# STM32F405.net
KiCad netlist of a schematic drawn in Altium Designer
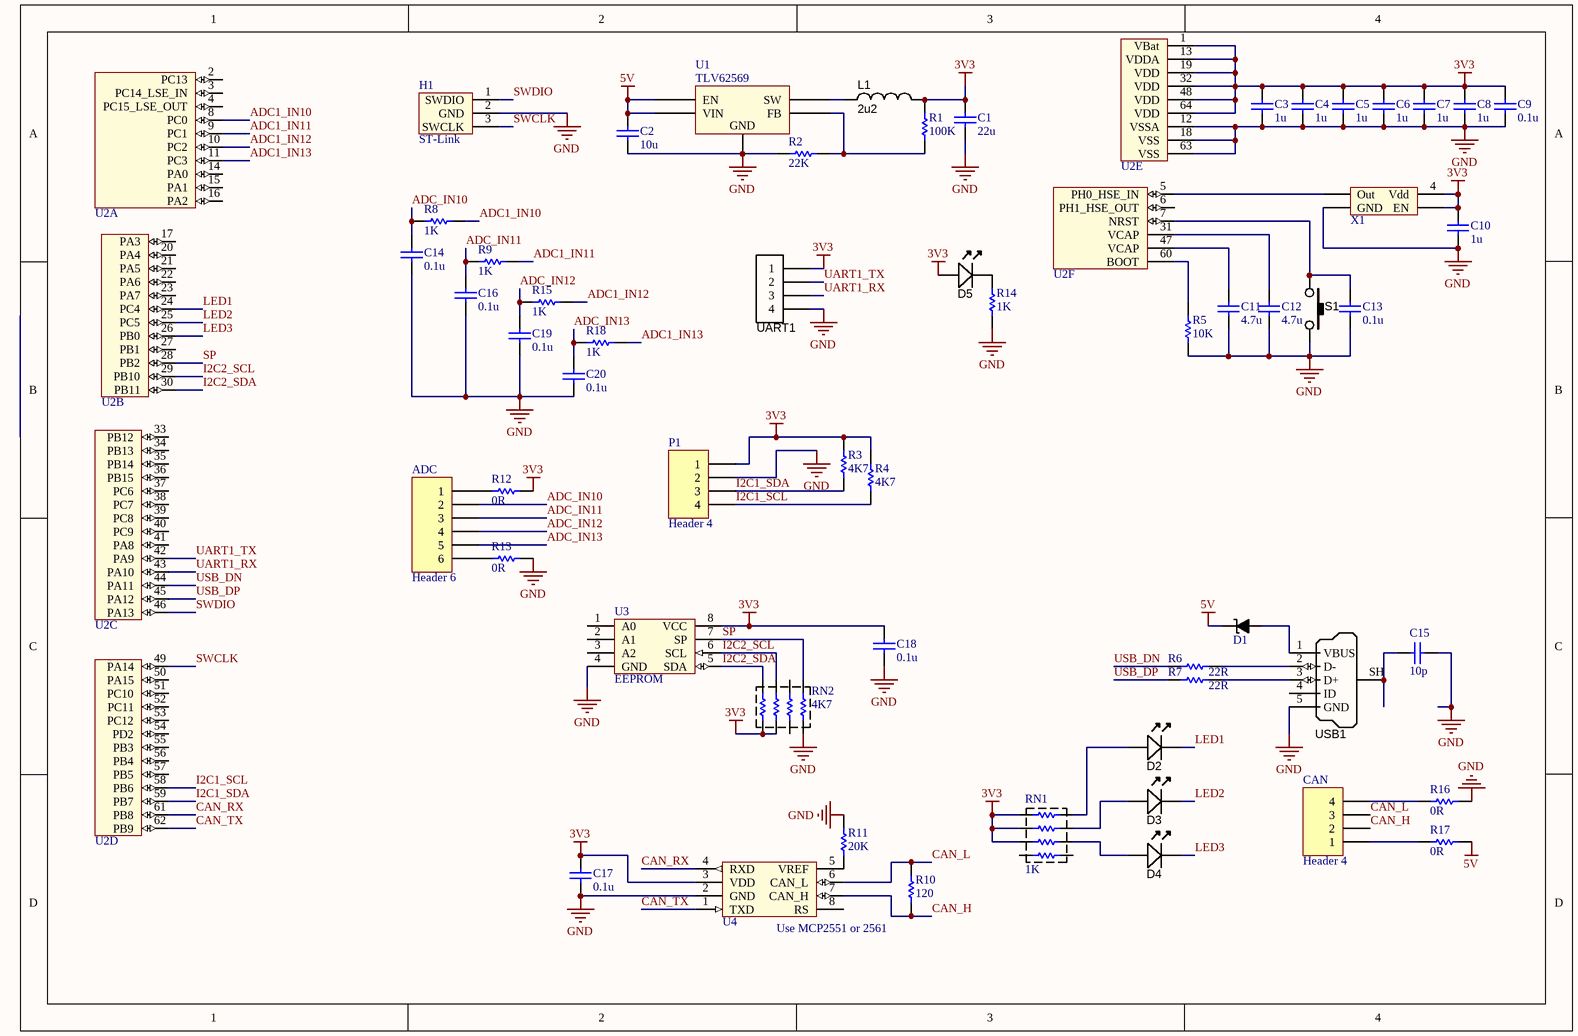
[diagram p0: STM32F405.SchDoc]

(export (version "E")
  (design (tool "Eeschema 10.0.6"))
  (components
    (comp (ref "ADC")
      (value "Header 6")
      (footprint "HDR1X6")
      (description "Header, 6-Pin")
      (fields (field (name "PUBLISHER") "Altium Limited"))
      (libsource (lib "Miscellaneous Connectors") (part "Header 6"))
    )
    (comp (ref "C1")
      (value "22u")
      (footprint "CAPC2012X135N")
      (description "Capacitor")
      (fields (field (name "Comment") "Cap") (field (name "PUBLISHER") "Altium Limited"))
      (libsource (lib "IOBoard_Low") (part "Cap"))
    )
    (comp (ref "C2")
      (value "10u")
      (footprint "CAPC2012X135N")
      (description "Capacitor")
      (fields (field (name "Comment") "Cap") (field (name "PUBLISHER") "Altium Limited"))
      (libsource (lib "IOBoard_Low") (part "Cap"))
    )
    (comp (ref "C3")
      (value "1u")
      (footprint "CAPC1608X90N")
      (description "Capacitor")
      (fields (field (name "Comment") "Cap") (field (name "PUBLISHER") "Altium Limited"))
      (libsource (lib "IOBoard_Low") (part "Cap"))
    )
    (comp (ref "C4")
      (value "1u")
      (footprint "CAPC1608X90N")
      (description "Capacitor")
      (fields (field (name "Comment") "Cap") (field (name "PUBLISHER") "Altium Limited"))
      (libsource (lib "IOBoard_Low") (part "Cap"))
    )
    (comp (ref "C5")
      (value "1u")
      (footprint "CAPC1608X90N")
      (description "Capacitor")
      (fields (field (name "Comment") "Cap") (field (name "PUBLISHER") "Altium Limited"))
      (libsource (lib "IOBoard_Low") (part "Cap"))
    )
    (comp (ref "C6")
      (value "1u")
      (footprint "CAPC1608X90N")
      (description "Capacitor")
      (fields (field (name "Comment") "Cap") (field (name "PUBLISHER") "Altium Limited"))
      (libsource (lib "IOBoard_Low") (part "Cap"))
    )
    (comp (ref "C7")
      (value "1u")
      (footprint "CAPC1608X90N")
      (description "Capacitor")
      (fields (field (name "Comment") "Cap") (field (name "PUBLISHER") "Altium Limited"))
      (libsource (lib "IOBoard_Low") (part "Cap"))
    )
    (comp (ref "C8")
      (value "1u")
      (footprint "CAPC1608X90N")
      (description "Capacitor")
      (fields (field (name "Comment") "Cap") (field (name "PUBLISHER") "Altium Limited"))
      (libsource (lib "IOBoard_Low") (part "Cap"))
    )
    (comp (ref "C9")
      (value "0.1u")
      (footprint "CAPC1608X90N")
      (description "Capacitor")
      (fields (field (name "Comment") "Cap") (field (name "PUBLISHER") "Altium Limited"))
      (libsource (lib "IOBoard_Low") (part "Cap"))
    )
    (comp (ref "C10")
      (value "1u")
      (footprint "CAPC1608X90N")
      (description "Capacitor")
      (fields (field (name "Comment") "Cap") (field (name "PUBLISHER") "Altium Limited"))
      (libsource (lib "IOBoard_Low") (part "Cap"))
    )
    (comp (ref "C11")
      (value "4.7u")
      (footprint "CAPC1608X90N")
      (description "Capacitor")
      (fields (field (name "Comment") "Cap") (field (name "PUBLISHER") "Altium Limited"))
      (libsource (lib "IOBoard_Low") (part "Cap"))
    )
    (comp (ref "C12")
      (value "4.7u")
      (footprint "CAPC1608X90N")
      (description "Capacitor")
      (fields (field (name "Comment") "Cap") (field (name "PUBLISHER") "Altium Limited"))
      (libsource (lib "IOBoard_Low") (part "Cap"))
    )
    (comp (ref "C13")
      (value "0.1u")
      (footprint "CAPC1608X90N")
      (description "Capacitor")
      (fields (field (name "Comment") "Cap") (field (name "PUBLISHER") "Altium Limited"))
      (libsource (lib "IOBoard_Low") (part "Cap"))
    )
    (comp (ref "C14")
      (value "0.1u")
      (footprint "CAPC1608X90N")
      (description "Capacitor")
      (fields (field (name "Comment") "Cap") (field (name "PUBLISHER") "Altium Limited"))
      (libsource (lib "IOBoard_Low") (part "Cap"))
    )
    (comp (ref "C15")
      (value "10p")
      (footprint "CAPC1608X90N")
      (description "Capacitor")
      (fields (field (name "Comment") "Cap") (field (name "PUBLISHER") "Altium Limited"))
      (libsource (lib "IOBoard_Low") (part "Cap"))
    )
    (comp (ref "C16")
      (value "0.1u")
      (footprint "CAPC1608X90N")
      (description "Capacitor")
      (fields (field (name "Comment") "Cap") (field (name "PUBLISHER") "Altium Limited"))
      (libsource (lib "IOBoard_Low") (part "Cap"))
    )
    (comp (ref "C17")
      (value "0.1u")
      (footprint "CAPC1608X90N")
      (description "Capacitor")
      (fields (field (name "Comment") "Cap") (field (name "PUBLISHER") "Altium Limited"))
      (libsource (lib "IOBoard_Low") (part "Cap"))
    )
    (comp (ref "C18")
      (value "0.1u")
      (footprint "CAPC1608X90N")
      (description "Capacitor")
      (fields (field (name "Comment") "Cap") (field (name "PUBLISHER") "Altium Limited"))
      (libsource (lib "IOBoard_Low") (part "Cap"))
    )
    (comp (ref "C19")
      (value "0.1u")
      (footprint "CAPC1608X90N")
      (description "Capacitor")
      (fields (field (name "Comment") "Cap") (field (name "PUBLISHER") "Altium Limited"))
      (libsource (lib "IOBoard_Low") (part "Cap"))
    )
    (comp (ref "C20")
      (value "0.1u")
      (footprint "CAPC1608X90N")
      (description "Capacitor")
      (fields (field (name "Comment") "Cap") (field (name "PUBLISHER") "Altium Limited"))
      (libsource (lib "IOBoard_Low") (part "Cap"))
    )
    (comp (ref "CAN")
      (value "Header 4")
      (footprint "1X4_HDR_2.00mm_PH")
      (description "Header, 4-Pin")
      (fields (field (name "PUBLISHER") "Altium Limited"))
      (libsource (lib "Miscellaneous Connectors") (part "Header 4"))
    )
    (comp (ref "D1")
      (value "diode")
      (footprint "DIODE_3216_70N")
      (description "100V 1A")
      (libsource (lib "IOBoard_Low") (part "SD1206S040S2R0"))
    )
    (comp (ref "D2")
      (value "LED_Green_GullWing")
      (footprint "LED-0805-A")
      (description "LED Gull-wing SMD High-intensity Green 450mcd 574nm")
      (libsource (lib "IOBoard") (part "LED_Green_GullWing"))
    )
    (comp (ref "D3")
      (value "LED_Green_GullWing")
      (footprint "LED-0805-A")
      (description "LED Gull-wing SMD High-intensity Green 450mcd 574nm")
      (libsource (lib "IOBoard") (part "LED_Green_GullWing"))
    )
    (comp (ref "D4")
      (value "LED_Green_GullWing")
      (footprint "LED-0805-A")
      (description "LED Gull-wing SMD High-intensity Green 450mcd 574nm")
      (libsource (lib "IOBoard") (part "LED_Green_GullWing"))
    )
    (comp (ref "D5")
      (value "LED_Green_GullWing")
      (footprint "LED-0805-A")
      (description "LED Gull-wing SMD High-intensity Green 450mcd 574nm")
      (libsource (lib "IOBoard") (part "LED_Green_GullWing"))
    )
    (comp (ref "H1")
      (value "ST-Link")
      (footprint "1x3POS_HEADER")
      (description "ST-Link header with silkscreen")
      (libsource (lib "IOBoard") (part "ST-Link"))
    )
    (comp (ref "L1")
      (value "2u2")
      (footprint "INDM3225X240N")
      (description "IHLP SMD 4040")
      (fields (field (name "Comment") "inductor"))
      (libsource (lib "IOBoard_Low") (part "INDC"))
    )
    (comp (ref "P1")
      (value "Header 4")
      (footprint "HDR1X4")
      (description "Header, 4-Pin")
      (fields (field (name "PUBLISHER") "Altium Limited"))
      (libsource (lib "") (part "Header 4_1"))
    )
    (comp (ref "R1")
      (value "100K")
      (footprint "RESC2012X70N")
      (description "Resistor")
      (fields (field (name "Comment") "Res1") (field (name "PUBLISHER") "Altium Limited"))
      (libsource (lib "IOBoard_Low") (part "Res1"))
    )
    (comp (ref "R2")
      (value "22K")
      (footprint "RESC2012X70N")
      (description "Resistor")
      (fields (field (name "Comment") "Res1") (field (name "PUBLISHER") "Altium Limited"))
      (libsource (lib "IOBoard_Low") (part "Res1"))
    )
    (comp (ref "R3")
      (value "4K7")
      (footprint "RESC1608X55N")
      (description "Resistor")
      (fields (field (name "Comment") "Res1") (field (name "PUBLISHER") "Altium Limited"))
      (libsource (lib "IOBoard_Low") (part "Res1"))
    )
    (comp (ref "R4")
      (value "4K7")
      (footprint "RESC1608X55N")
      (description "Resistor")
      (fields (field (name "Comment") "Res1") (field (name "PUBLISHER") "Altium Limited"))
      (libsource (lib "IOBoard_Low") (part "Res1"))
    )
    (comp (ref "R5")
      (value "10K")
      (footprint "RESC1608X55N")
      (description "Resistor")
      (fields (field (name "Comment") "Res1") (field (name "PUBLISHER") "Altium Limited"))
      (libsource (lib "IOBoard_Low") (part "Res1"))
    )
    (comp (ref "R6")
      (value "22R")
      (footprint "RESC1608X55N")
      (description "Resistor")
      (fields (field (name "Comment") "Res1") (field (name "PUBLISHER") "Altium Limited"))
      (libsource (lib "IOBoard_Low") (part "Res1"))
    )
    (comp (ref "R7")
      (value "22R")
      (footprint "RESC1608X55N")
      (description "Resistor")
      (fields (field (name "Comment") "Res1") (field (name "PUBLISHER") "Altium Limited"))
      (libsource (lib "IOBoard_Low") (part "Res1"))
    )
    (comp (ref "R8")
      (value "1K")
      (footprint "RESC1608X55N")
      (description "Resistor")
      (fields (field (name "Comment") "Res1") (field (name "PUBLISHER") "Altium Limited"))
      (libsource (lib "IOBoard_Low") (part "Res1"))
    )
    (comp (ref "R9")
      (value "1K")
      (footprint "RESC1608X55N")
      (description "Resistor")
      (fields (field (name "Comment") "Res1") (field (name "PUBLISHER") "Altium Limited"))
      (libsource (lib "IOBoard_Low") (part "Res1"))
    )
    (comp (ref "R10")
      (value "120")
      (footprint "RESC1608X55N")
      (description "Resistor")
      (fields (field (name "Comment") "Res1") (field (name "PUBLISHER") "Altium Limited"))
      (libsource (lib "IOBoard_Low") (part "Res1"))
    )
    (comp (ref "R11")
      (value "20K")
      (footprint "RESC1608X55N")
      (description "Resistor")
      (fields (field (name "Comment") "Res1") (field (name "PUBLISHER") "Altium Limited"))
      (libsource (lib "IOBoard_Low") (part "Res1"))
    )
    (comp (ref "R12")
      (value "0R")
      (footprint "RESC1608X55N")
      (description "Resistor")
      (fields (field (name "Comment") "Res1") (field (name "PUBLISHER") "Altium Limited"))
      (libsource (lib "IOBoard_Low") (part "Res1"))
    )
    (comp (ref "R13")
      (value "0R")
      (footprint "RESC1608X55N")
      (description "Resistor")
      (fields (field (name "Comment") "Res1") (field (name "PUBLISHER") "Altium Limited"))
      (libsource (lib "IOBoard_Low") (part "Res1"))
    )
    (comp (ref "R14")
      (value "1K")
      (footprint "RESC1608X55N")
      (description "Resistor")
      (fields (field (name "Comment") "Res1") (field (name "PUBLISHER") "Altium Limited"))
      (libsource (lib "IOBoard_Low") (part "Res1"))
    )
    (comp (ref "R15")
      (value "1K")
      (footprint "RESC1608X55N")
      (description "Resistor")
      (fields (field (name "Comment") "Res1") (field (name "PUBLISHER") "Altium Limited"))
      (libsource (lib "IOBoard_Low") (part "Res1"))
    )
    (comp (ref "R16")
      (value "0R")
      (footprint "RESC1608X55N")
      (description "Resistor")
      (fields (field (name "Comment") "Res1") (field (name "PUBLISHER") "Altium Limited"))
      (libsource (lib "IOBoard_Low") (part "Res1"))
    )
    (comp (ref "R17")
      (value "0R")
      (footprint "RESC1608X55N")
      (description "Resistor")
      (fields (field (name "Comment") "Res1") (field (name "PUBLISHER") "Altium Limited"))
      (libsource (lib "IOBoard_Low") (part "Res1"))
    )
    (comp (ref "R18")
      (value "1K")
      (footprint "RESC1608X55N")
      (description "Resistor")
      (fields (field (name "Comment") "Res1") (field (name "PUBLISHER") "Altium Limited"))
      (libsource (lib "IOBoard_Low") (part "Res1"))
    )
    (comp (ref "RN1")
      (value "1K")
      (footprint "RESCAXS50P160X320X70-8N")
      (fields (field (name "Comment") "resistor network"))
      (libsource (lib "IOBoard") (part "RES_NET"))
    )
    (comp (ref "RN2")
      (value "4K7")
      (footprint "RESCAXS50P160X320X70-8N")
      (fields (field (name "Comment") "resistor network"))
      (libsource (lib "IOBoard") (part "RES_NET"))
    )
    (comp (ref "S1")
      (value "SW_THT_PB_4.3mm")
      (footprint "TACT_SWT-SMD-4.4")
      (description "Switch, tact, 4.3mm stem")
      (libsource (lib "IOBoard") (part "SW_THT_PB_4.3mm"))
    )
    (comp (ref "U1")
      (value "TLV62569")
      (footprint "SOT23-5")
      (description "2-A High Efficiency Synchronous Buck Converter in SOT Package")
      (fields (field (name "MANUFACTURER") "TI"))
      (libsource (lib "IOBoard") (part "TLV62569"))
    )
    (comp (ref "U2")
      (value "STM32F405RE")
      (footprint "LQFP64")
      (description "STM32F405RE 64 pin package, Cortex M4 core with up to")
      (libsource (lib "IOBoard") (part "STM32F405RE"))
    )
    (comp (ref "U3")
      (value "EEPROM")
      (footprint "SOP8")
      (description "64K EEPROM")
      (libsource (lib "IOBoard") (part "AT24C64"))
    )
    (comp (ref "U4")
      (value "SN65HVD23x")
      (footprint "SOIC127P600X175-8AN")
      (description "SN65HVD23x 3.3-V CAN Bus Transceivers")
      (libsource (lib "IOBoard") (part "SN65HVD23x"))
    )
    (comp (ref "UART1")
      (value "Programmer")
      (footprint "1X4_HDR_2.00mm_PH")
      (description "Header 4-pin")
      (libsource (lib "IOBoard") (part "Header4P"))
    )
    (comp (ref "USB1")
      (value "USB Micro Type B")
      (footprint "USB_MICRO-B")
      (description "Connector SMD USB Micro Type B middle mount")
      (libsource (lib "IOBoard") (part "USB_Micro_TypeB"))
    )
    (comp (ref "X1")
      (value "ASE-8.000MHZ-LC-T")
      (footprint "ASE Series")
      (description "8MHz")
      (libsource (lib "IOBoard") (part "ASE-8.000MHZ-LC-T"))
    )
  )
  (nets
    (net (code "1") (name "/ADC1_IN10") (class "Default")
      (node (ref "R8") (pin "1") (pinfunction "1_1") (pintype "passive"))
      (node (ref "U2") (pin "8") (pinfunction "PC0_8") (pintype "bidirectional"))
    )
    (net (code "2") (name "/ADC1_IN11") (class "Default")
      (node (ref "R9") (pin "1") (pinfunction "1_1") (pintype "passive"))
      (node (ref "U2") (pin "9") (pinfunction "PC1_9") (pintype "bidirectional"))
    )
    (net (code "3") (name "/ADC1_IN12") (class "Default")
      (node (ref "R15") (pin "1") (pinfunction "1_1") (pintype "passive"))
      (node (ref "U2") (pin "10") (pinfunction "PC2_10") (pintype "bidirectional"))
    )
    (net (code "4") (name "/ADC1_IN13") (class "Default")
      (node (ref "R18") (pin "1") (pinfunction "1_1") (pintype "passive"))
      (node (ref "U2") (pin "11") (pinfunction "PC3_11") (pintype "bidirectional"))
    )
    (net (code "5") (name "/ADC_IN10") (class "Default")
      (node (ref "ADC") (pin "2") (pinfunction "2_2") (pintype "passive"))
      (node (ref "C14") (pin "2") (pinfunction "2_2") (pintype "passive"))
      (node (ref "R8") (pin "2") (pinfunction "2_2") (pintype "passive"))
    )
    (net (code "6") (name "/ADC_IN11") (class "Default")
      (node (ref "ADC") (pin "3") (pinfunction "3_3") (pintype "passive"))
      (node (ref "C16") (pin "2") (pinfunction "2_2") (pintype "passive"))
      (node (ref "R9") (pin "2") (pinfunction "2_2") (pintype "passive"))
    )
    (net (code "7") (name "/ADC_IN12") (class "Default")
      (node (ref "ADC") (pin "4") (pinfunction "4_4") (pintype "passive"))
      (node (ref "C19") (pin "2") (pinfunction "2_2") (pintype "passive"))
      (node (ref "R15") (pin "2") (pinfunction "2_2") (pintype "passive"))
    )
    (net (code "8") (name "/ADC_IN13") (class "Default")
      (node (ref "ADC") (pin "5") (pinfunction "5_5") (pintype "passive"))
      (node (ref "C20") (pin "2") (pinfunction "2_2") (pintype "passive"))
      (node (ref "R18") (pin "2") (pinfunction "2_2") (pintype "passive"))
    )
    (net (code "9") (name "/CAN_H") (class "Default")
      (node (ref "CAN") (pin "2") (pinfunction "2_2") (pintype "passive"))
      (node (ref "R10") (pin "1") (pinfunction "1_1") (pintype "passive"))
      (node (ref "U4") (pin "7") (pinfunction "CAN_H_7") (pintype "bidirectional"))
    )
    (net (code "10") (name "/CAN_L") (class "Default")
      (node (ref "CAN") (pin "3") (pinfunction "3_3") (pintype "passive"))
      (node (ref "R10") (pin "2") (pinfunction "2_2") (pintype "passive"))
      (node (ref "U4") (pin "6") (pinfunction "CAN_L_6") (pintype "bidirectional"))
    )
    (net (code "11") (name "/CAN_RX") (class "Default")
      (node (ref "U2") (pin "61") (pinfunction "PB8_61") (pintype "bidirectional"))
      (node (ref "U4") (pin "4") (pinfunction "RXD_4") (pintype "output"))
    )
    (net (code "12") (name "/CAN_TX") (class "Default")
      (node (ref "U2") (pin "62") (pinfunction "PB9_62") (pintype "bidirectional"))
      (node (ref "U4") (pin "1") (pinfunction "TXD_1") (pintype "input"))
    )
    (net (code "13") (name "/I2C1_SCL") (class "Default")
      (node (ref "P1") (pin "4") (pinfunction "4_4") (pintype "passive"))
      (node (ref "R4") (pin "1") (pinfunction "1_1") (pintype "passive"))
      (node (ref "U2") (pin "58") (pinfunction "PB6_58") (pintype "bidirectional"))
    )
    (net (code "14") (name "/I2C1_SDA") (class "Default")
      (node (ref "P1") (pin "3") (pinfunction "3_3") (pintype "passive"))
      (node (ref "R3") (pin "1") (pinfunction "1_1") (pintype "passive"))
      (node (ref "U2") (pin "59") (pinfunction "PB7_59") (pintype "bidirectional"))
    )
    (net (code "15") (name "/I2C2_SCL") (class "Default")
      (node (ref "RN2") (pin "7") (pinfunction "7_7") (pintype "power_in"))
      (node (ref "U2") (pin "29") (pinfunction "PB10_29") (pintype "bidirectional"))
      (node (ref "U3") (pin "6") (pinfunction "SCL_6") (pintype "input"))
    )
    (net (code "16") (name "/I2C2_SDA") (class "Default")
      (node (ref "RN2") (pin "8") (pinfunction "8_8") (pintype "power_in"))
      (node (ref "U2") (pin "30") (pinfunction "PB11_30") (pintype "bidirectional"))
      (node (ref "U3") (pin "5") (pinfunction "SDA_5") (pintype "bidirectional"))
    )
    (net (code "17") (name "/LED1") (class "Default")
      (node (ref "D2") (pin "K") (pinfunction "K_K") (pintype "passive"))
      (node (ref "U2") (pin "24") (pinfunction "PC4_24") (pintype "bidirectional"))
    )
    (net (code "18") (name "/LED2") (class "Default")
      (node (ref "D3") (pin "K") (pinfunction "K_K") (pintype "passive"))
      (node (ref "U2") (pin "25") (pinfunction "PC5_25") (pintype "bidirectional"))
    )
    (net (code "19") (name "/LED3") (class "Default")
      (node (ref "D4") (pin "K") (pinfunction "K_K") (pintype "passive"))
      (node (ref "U2") (pin "26") (pinfunction "PB0_26") (pintype "bidirectional"))
    )
    (net (code "20") (name "/SP") (class "Default")
      (node (ref "RN2") (pin "5") (pinfunction "5_5") (pintype "power_in"))
      (node (ref "U2") (pin "28") (pinfunction "PB2_28") (pintype "bidirectional"))
      (node (ref "U3") (pin "7") (pinfunction "SP_7") (pintype "passive"))
    )
    (net (code "21") (name "/SWCLK") (class "Default")
      (node (ref "H1") (pin "3") (pinfunction "SWCLK_3") (pintype "power_in"))
      (node (ref "U2") (pin "49") (pinfunction "PA14_49") (pintype "bidirectional"))
    )
    (net (code "22") (name "/SWDIO") (class "Default")
      (node (ref "H1") (pin "1") (pinfunction "SWDIO_1") (pintype "power_in"))
      (node (ref "U2") (pin "46") (pinfunction "PA13_46") (pintype "bidirectional"))
    )
    (net (code "23") (name "/UART1_RX") (class "Default")
      (node (ref "U2") (pin "43") (pinfunction "PA10_43") (pintype "bidirectional"))
      (node (ref "UART1") (pin "3") (pinfunction "3_3") (pintype "passive"))
    )
    (net (code "24") (name "/UART1_TX") (class "Default")
      (node (ref "U2") (pin "42") (pinfunction "PA9_42") (pintype "bidirectional"))
      (node (ref "UART1") (pin "2") (pinfunction "2_2") (pintype "passive"))
    )
    (net (code "25") (name "/USB_DN") (class "Default")
      (node (ref "R6") (pin "1") (pinfunction "1_1") (pintype "passive"))
      (node (ref "U2") (pin "44") (pinfunction "PA11_44") (pintype "bidirectional"))
    )
    (net (code "26") (name "/USB_DP") (class "Default")
      (node (ref "R7") (pin "1") (pinfunction "1_1") (pintype "passive"))
      (node (ref "U2") (pin "45") (pinfunction "PA12_45") (pintype "bidirectional"))
    )
    (net (code "27") (name "3V3") (class "Default")
      (node (ref "C1") (pin "2") (pinfunction "2_2") (pintype "passive"))
      (node (ref "C10") (pin "2") (pinfunction "2_2") (pintype "passive"))
      (node (ref "C17") (pin "2") (pinfunction "2_2") (pintype "passive"))
      (node (ref "C18") (pin "1") (pinfunction "1_1") (pintype "passive"))
      (node (ref "C3") (pin "2") (pinfunction "2_2") (pintype "passive"))
      (node (ref "C4") (pin "2") (pinfunction "2_2") (pintype "passive"))
      (node (ref "C5") (pin "2") (pinfunction "2_2") (pintype "passive"))
      (node (ref "C6") (pin "2") (pinfunction "2_2") (pintype "passive"))
      (node (ref "C7") (pin "2") (pinfunction "2_2") (pintype "passive"))
      (node (ref "C8") (pin "2") (pinfunction "2_2") (pintype "passive"))
      (node (ref "C9") (pin "2") (pinfunction "2_2") (pintype "passive"))
      (node (ref "D5") (pin "A") (pinfunction "A_A") (pintype "passive"))
      (node (ref "L1") (pin "2") (pinfunction "2_2") (pintype "passive"))
      (node (ref "P1") (pin "1") (pinfunction "1_1") (pintype "passive"))
      (node (ref "R1") (pin "2") (pinfunction "2_2") (pintype "passive"))
      (node (ref "R12") (pin "2") (pinfunction "2_2") (pintype "passive"))
      (node (ref "R3") (pin "2") (pinfunction "2_2") (pintype "passive"))
      (node (ref "R4") (pin "2") (pinfunction "2_2") (pintype "passive"))
      (node (ref "RN1") (pin "1") (pinfunction "1_1") (pintype "power_in"))
      (node (ref "RN1") (pin "2") (pinfunction "2_2") (pintype "power_in"))
      (node (ref "RN1") (pin "3") (pinfunction "3_3") (pintype "power_in"))
      (node (ref "RN2") (pin "1") (pinfunction "1_1") (pintype "power_in"))
      (node (ref "RN2") (pin "2") (pinfunction "2_2") (pintype "power_in"))
      (node (ref "U2") (pin "1") (pinfunction "VBat_1") (pintype "power_in"))
      (node (ref "U2") (pin "13") (pinfunction "VDDA_13") (pintype "power_in"))
      (node (ref "U2") (pin "19") (pinfunction "VDD_19") (pintype "power_in"))
      (node (ref "U2") (pin "32") (pinfunction "VDD_32") (pintype "power_in"))
      (node (ref "U2") (pin "48") (pinfunction "VDD_48") (pintype "power_in"))
      (node (ref "U2") (pin "64") (pinfunction "VDD_64") (pintype "power_in"))
      (node (ref "U3") (pin "8") (pinfunction "VCC_8") (pintype "power_in"))
      (node (ref "U4") (pin "3") (pinfunction "VDD_3") (pintype "power_in"))
      (node (ref "UART1") (pin "1") (pinfunction "1_1") (pintype "passive"))
      (node (ref "X1") (pin "1") (pinfunction "EN_1") (pintype "passive"))
      (node (ref "X1") (pin "4") (pinfunction "Vdd_4") (pintype "passive"))
    )
    (net (code "28") (name "5V") (class "Default")
      (node (ref "C2") (pin "2") (pinfunction "2_2") (pintype "passive"))
      (node (ref "D1") (pin "K") (pinfunction "Cathode_K") (pintype "passive"))
      (node (ref "R17") (pin "2") (pinfunction "2_2") (pintype "passive"))
      (node (ref "U1") (pin "1") (pinfunction "EN_1") (pintype "passive"))
      (node (ref "U1") (pin "4") (pinfunction "VIN_4") (pintype "passive"))
    )
    (net (code "29") (name "GND") (class "Default")
      (node (ref "C1") (pin "1") (pinfunction "1_1") (pintype "passive"))
      (node (ref "C10") (pin "1") (pinfunction "1_1") (pintype "passive"))
      (node (ref "C11") (pin "1") (pinfunction "1_1") (pintype "passive"))
      (node (ref "C12") (pin "1") (pinfunction "1_1") (pintype "passive"))
      (node (ref "C13") (pin "1") (pinfunction "1_1") (pintype "passive"))
      (node (ref "C14") (pin "1") (pinfunction "1_1") (pintype "passive"))
      (node (ref "C15") (pin "2") (pinfunction "2_2") (pintype "passive"))
      (node (ref "C16") (pin "1") (pinfunction "1_1") (pintype "passive"))
      (node (ref "C17") (pin "1") (pinfunction "1_1") (pintype "passive"))
      (node (ref "C18") (pin "2") (pinfunction "2_2") (pintype "passive"))
      (node (ref "C19") (pin "1") (pinfunction "1_1") (pintype "passive"))
      (node (ref "C2") (pin "1") (pinfunction "1_1") (pintype "passive"))
      (node (ref "C20") (pin "1") (pinfunction "1_1") (pintype "passive"))
      (node (ref "C3") (pin "1") (pinfunction "1_1") (pintype "passive"))
      (node (ref "C4") (pin "1") (pinfunction "1_1") (pintype "passive"))
      (node (ref "C5") (pin "1") (pinfunction "1_1") (pintype "passive"))
      (node (ref "C6") (pin "1") (pinfunction "1_1") (pintype "passive"))
      (node (ref "C7") (pin "1") (pinfunction "1_1") (pintype "passive"))
      (node (ref "C8") (pin "1") (pinfunction "1_1") (pintype "passive"))
      (node (ref "C9") (pin "1") (pinfunction "1_1") (pintype "passive"))
      (node (ref "H1") (pin "2") (pinfunction "GND_2") (pintype "power_in"))
      (node (ref "P1") (pin "2") (pinfunction "2_2") (pintype "passive"))
      (node (ref "R11") (pin "1") (pinfunction "1_1") (pintype "passive"))
      (node (ref "R13") (pin "2") (pinfunction "2_2") (pintype "passive"))
      (node (ref "R14") (pin "2") (pinfunction "2_2") (pintype "passive"))
      (node (ref "R16") (pin "2") (pinfunction "2_2") (pintype "passive"))
      (node (ref "R2") (pin "1") (pinfunction "1_1") (pintype "passive"))
      (node (ref "R5") (pin "1") (pinfunction "1_1") (pintype "passive"))
      (node (ref "RN2") (pin "4") (pinfunction "4_4") (pintype "power_in"))
      (node (ref "S1") (pin "2") (pintype "passive"))
      (node (ref "U1") (pin "2") (pinfunction "GND_2") (pintype "passive"))
      (node (ref "U2") (pin "12") (pinfunction "VSSA_12") (pintype "power_in"))
      (node (ref "U2") (pin "18") (pinfunction "VSS_18") (pintype "power_in"))
      (node (ref "U2") (pin "63") (pinfunction "VSS_63") (pintype "power_in"))
      (node (ref "U3") (pin "4") (pinfunction "GND_4") (pintype "power_in"))
      (node (ref "U4") (pin "2") (pinfunction "GND_2") (pintype "power_in"))
      (node (ref "UART1") (pin "4") (pinfunction "4_4") (pintype "passive"))
      (node (ref "USB1") (pin "5") (pinfunction "GND_5") (pintype "power_in"))
      (node (ref "X1") (pin "2") (pinfunction "GND_2") (pintype "passive"))
    )
    (net (code "30") (name "Net-(ADC-Pad1)") (class "Default")
      (node (ref "ADC") (pin "1") (pinfunction "1_1") (pintype "passive"))
      (node (ref "R12") (pin "1") (pinfunction "1_1") (pintype "passive"))
    )
    (net (code "31") (name "Net-(ADC-Pad6)") (class "Default")
      (node (ref "ADC") (pin "6") (pinfunction "6_6") (pintype "passive"))
      (node (ref "R13") (pin "1") (pinfunction "1_1") (pintype "passive"))
    )
    (net (code "32") (name "Net-(C11-Pad2)") (class "Default")
      (node (ref "C11") (pin "2") (pinfunction "2_2") (pintype "passive"))
      (node (ref "U2") (pin "47") (pinfunction "VCAP_47") (pintype "power_in"))
    )
    (net (code "33") (name "Net-(C12-Pad2)") (class "Default")
      (node (ref "C12") (pin "2") (pinfunction "2_2") (pintype "passive"))
      (node (ref "U2") (pin "31") (pinfunction "VCAP_31") (pintype "power_in"))
    )
    (net (code "34") (name "Net-(CAN-Pad1)") (class "Default")
      (node (ref "CAN") (pin "1") (pinfunction "1_1") (pintype "passive"))
      (node (ref "R17") (pin "1") (pinfunction "1_1") (pintype "passive"))
    )
    (net (code "35") (name "Net-(CAN-Pad4)") (class "Default")
      (node (ref "CAN") (pin "4") (pinfunction "4_4") (pintype "passive"))
      (node (ref "R16") (pin "1") (pinfunction "1_1") (pintype "passive"))
    )
    (net (code "36") (name "Net-(D1-Anode)") (class "Default")
      (node (ref "D1") (pin "A") (pinfunction "Anode_A") (pintype "passive"))
      (node (ref "USB1") (pin "1") (pinfunction "VBUS_1") (pintype "power_in"))
    )
    (net (code "37") (name "Net-(D2-PadA)") (class "Default")
      (node (ref "D2") (pin "A") (pinfunction "A_A") (pintype "passive"))
      (node (ref "RN1") (pin "8") (pinfunction "8_8") (pintype "power_in"))
    )
    (net (code "38") (name "Net-(D3-PadA)") (class "Default")
      (node (ref "D3") (pin "A") (pinfunction "A_A") (pintype "passive"))
      (node (ref "RN1") (pin "7") (pinfunction "7_7") (pintype "power_in"))
    )
    (net (code "39") (name "Net-(D4-PadA)") (class "Default")
      (node (ref "D4") (pin "A") (pinfunction "A_A") (pintype "passive"))
      (node (ref "RN1") (pin "6") (pinfunction "6_6") (pintype "power_in"))
    )
    (net (code "40") (name "Net-(D5-PadK)") (class "Default")
      (node (ref "D5") (pin "K") (pinfunction "K_K") (pintype "passive"))
      (node (ref "R14") (pin "1") (pinfunction "1_1") (pintype "passive"))
    )
    (net (code "41") (name "Net-(U1-FB)") (class "Default")
      (node (ref "R1") (pin "1") (pinfunction "1_1") (pintype "passive"))
      (node (ref "R2") (pin "2") (pinfunction "2_2") (pintype "passive"))
      (node (ref "U1") (pin "5") (pinfunction "FB_5") (pintype "passive"))
    )
    (net (code "42") (name "Net-(U1-SW)") (class "Default")
      (node (ref "L1") (pin "1") (pinfunction "1_1") (pintype "passive"))
      (node (ref "U1") (pin "3") (pinfunction "SW_3") (pintype "passive"))
    )
    (net (code "43") (name "Net-(U2F-BOOT)") (class "Default")
      (node (ref "R5") (pin "2") (pinfunction "2_2") (pintype "passive"))
      (node (ref "U2") (pin "60") (pinfunction "BOOT_60") (pintype "passive"))
    )
    (net (code "44") (name "Net-(U2F-NRST)") (class "Default")
      (node (ref "C13") (pin "2") (pinfunction "2_2") (pintype "passive"))
      (node (ref "S1") (pin "1") (pintype "passive"))
      (node (ref "U2") (pin "7") (pinfunction "NRST_7") (pintype "bidirectional"))
    )
    (net (code "45") (name "Net-(U2F-PH0_HSE_IN)") (class "Default")
      (node (ref "U2") (pin "5") (pinfunction "PH0_HSE_IN_5") (pintype "bidirectional"))
      (node (ref "X1") (pin "3") (pinfunction "Out_3") (pintype "passive"))
    )
    (net (code "46") (name "Net-(U4-VREF)") (class "Default")
      (node (ref "R11") (pin "2") (pinfunction "2_2") (pintype "passive"))
      (node (ref "U4") (pin "5") (pinfunction "VREF_5") (pintype "passive"))
    )
    (net (code "47") (name "Net-(USB1-D+)") (class "Default")
      (node (ref "R7") (pin "2") (pinfunction "2_2") (pintype "passive"))
      (node (ref "USB1") (pin "3") (pinfunction "D+_3") (pintype "bidirectional"))
    )
    (net (code "48") (name "Net-(USB1-D-)") (class "Default")
      (node (ref "R6") (pin "2") (pinfunction "2_2") (pintype "passive"))
      (node (ref "USB1") (pin "2") (pinfunction "D-_2") (pintype "bidirectional"))
    )
    (net (code "49") (name "Net-(USB1-Shell)") (class "Default")
      (node (ref "C15") (pin "1") (pinfunction "1_1") (pintype "passive"))
      (node (ref "USB1") (pin "SH") (pinfunction "Shell_SH") (pintype "passive"))
    )
    (net (code "50") (name "unconnected-(RN1-Pad4)") (class "Default")
      (node (ref "RN1") (pin "4") (pinfunction "4_4") (pintype "power_in"))
    )
    (net (code "51") (name "unconnected-(RN1-Pad5)") (class "Default")
      (node (ref "RN1") (pin "5") (pinfunction "5_5") (pintype "power_in"))
    )
    (net (code "52") (name "unconnected-(RN2-Pad3)") (class "Default")
      (node (ref "RN2") (pin "3") (pinfunction "3_3") (pintype "power_in"))
    )
    (net (code "53") (name "unconnected-(RN2-Pad6)") (class "Default")
      (node (ref "RN2") (pin "6") (pinfunction "6_6") (pintype "power_in"))
    )
    (net (code "54") (name "unconnected-(U2A-PA0-Pad14)") (class "Default")
      (node (ref "U2") (pin "14") (pinfunction "PA0_14") (pintype "bidirectional"))
    )
    (net (code "55") (name "unconnected-(U2A-PA1-Pad15)") (class "Default")
      (node (ref "U2") (pin "15") (pinfunction "PA1_15") (pintype "bidirectional"))
    )
    (net (code "56") (name "unconnected-(U2A-PA2-Pad16)") (class "Default")
      (node (ref "U2") (pin "16") (pinfunction "PA2_16") (pintype "bidirectional"))
    )
    (net (code "57") (name "unconnected-(U2A-PC13-Pad2)") (class "Default")
      (node (ref "U2") (pin "2") (pinfunction "PC13_2") (pintype "bidirectional"))
    )
    (net (code "58") (name "unconnected-(U2A-PC14_LSE_IN-Pad3)") (class "Default")
      (node (ref "U2") (pin "3") (pinfunction "PC14_LSE_IN_3") (pintype "bidirectional"))
    )
    (net (code "59") (name "unconnected-(U2A-PC15_LSE_OUT-Pad4)") (class "Default")
      (node (ref "U2") (pin "4") (pinfunction "PC15_LSE_OUT_4") (pintype "bidirectional"))
    )
    (net (code "60") (name "unconnected-(U2B-PA3-Pad17)") (class "Default")
      (node (ref "U2") (pin "17") (pinfunction "PA3_17") (pintype "bidirectional"))
    )
    (net (code "61") (name "unconnected-(U2B-PA4-Pad20)") (class "Default")
      (node (ref "U2") (pin "20") (pinfunction "PA4_20") (pintype "bidirectional"))
    )
    (net (code "62") (name "unconnected-(U2B-PA5-Pad21)") (class "Default")
      (node (ref "U2") (pin "21") (pinfunction "PA5_21") (pintype "bidirectional"))
    )
    (net (code "63") (name "unconnected-(U2B-PA6-Pad22)") (class "Default")
      (node (ref "U2") (pin "22") (pinfunction "PA6_22") (pintype "bidirectional"))
    )
    (net (code "64") (name "unconnected-(U2B-PA7-Pad23)") (class "Default")
      (node (ref "U2") (pin "23") (pinfunction "PA7_23") (pintype "bidirectional"))
    )
    (net (code "65") (name "unconnected-(U2B-PB1-Pad27)") (class "Default")
      (node (ref "U2") (pin "27") (pinfunction "PB1_27") (pintype "bidirectional"))
    )
    (net (code "66") (name "unconnected-(U2C-PA8-Pad41)") (class "Default")
      (node (ref "U2") (pin "41") (pinfunction "PA8_41") (pintype "bidirectional"))
    )
    (net (code "67") (name "unconnected-(U2C-PB12-Pad33)") (class "Default")
      (node (ref "U2") (pin "33") (pinfunction "PB12_33") (pintype "bidirectional"))
    )
    (net (code "68") (name "unconnected-(U2C-PB13-Pad34)") (class "Default")
      (node (ref "U2") (pin "34") (pinfunction "PB13_34") (pintype "bidirectional"))
    )
    (net (code "69") (name "unconnected-(U2C-PB14-Pad35)") (class "Default")
      (node (ref "U2") (pin "35") (pinfunction "PB14_35") (pintype "bidirectional"))
    )
    (net (code "70") (name "unconnected-(U2C-PB15-Pad36)") (class "Default")
      (node (ref "U2") (pin "36") (pinfunction "PB15_36") (pintype "bidirectional"))
    )
    (net (code "71") (name "unconnected-(U2C-PC6-Pad37)") (class "Default")
      (node (ref "U2") (pin "37") (pinfunction "PC6_37") (pintype "bidirectional"))
    )
    (net (code "72") (name "unconnected-(U2C-PC7-Pad38)") (class "Default")
      (node (ref "U2") (pin "38") (pinfunction "PC7_38") (pintype "bidirectional"))
    )
    (net (code "73") (name "unconnected-(U2C-PC8-Pad39)") (class "Default")
      (node (ref "U2") (pin "39") (pinfunction "PC8_39") (pintype "bidirectional"))
    )
    (net (code "74") (name "unconnected-(U2C-PC9-Pad40)") (class "Default")
      (node (ref "U2") (pin "40") (pinfunction "PC9_40") (pintype "bidirectional"))
    )
    (net (code "75") (name "unconnected-(U2D-PA15-Pad50)") (class "Default")
      (node (ref "U2") (pin "50") (pinfunction "PA15_50") (pintype "bidirectional"))
    )
    (net (code "76") (name "unconnected-(U2D-PB3-Pad55)") (class "Default")
      (node (ref "U2") (pin "55") (pinfunction "PB3_55") (pintype "bidirectional"))
    )
    (net (code "77") (name "unconnected-(U2D-PB4-Pad56)") (class "Default")
      (node (ref "U2") (pin "56") (pinfunction "PB4_56") (pintype "bidirectional"))
    )
    (net (code "78") (name "unconnected-(U2D-PB5-Pad57)") (class "Default")
      (node (ref "U2") (pin "57") (pinfunction "PB5_57") (pintype "bidirectional"))
    )
    (net (code "79") (name "unconnected-(U2D-PC10-Pad51)") (class "Default")
      (node (ref "U2") (pin "51") (pinfunction "PC10_51") (pintype "bidirectional"))
    )
    (net (code "80") (name "unconnected-(U2D-PC11-Pad52)") (class "Default")
      (node (ref "U2") (pin "52") (pinfunction "PC11_52") (pintype "bidirectional"))
    )
    (net (code "81") (name "unconnected-(U2D-PC12-Pad53)") (class "Default")
      (node (ref "U2") (pin "53") (pinfunction "PC12_53") (pintype "bidirectional"))
    )
    (net (code "82") (name "unconnected-(U2D-PD2-Pad54)") (class "Default")
      (node (ref "U2") (pin "54") (pinfunction "PD2_54") (pintype "bidirectional"))
    )
    (net (code "83") (name "unconnected-(U2F-PH1_HSE_OUT-Pad6)") (class "Default")
      (node (ref "U2") (pin "6") (pinfunction "PH1_HSE_OUT_6") (pintype "bidirectional"))
    )
    (net (code "84") (name "unconnected-(U3-A0-Pad1)") (class "Default")
      (node (ref "U3") (pin "1") (pinfunction "A0_1") (pintype "passive"))
    )
    (net (code "85") (name "unconnected-(U3-A1-Pad2)") (class "Default")
      (node (ref "U3") (pin "2") (pinfunction "A1_2") (pintype "passive"))
    )
    (net (code "86") (name "unconnected-(U3-A2-Pad3)") (class "Default")
      (node (ref "U3") (pin "3") (pinfunction "A2_3") (pintype "passive"))
    )
    (net (code "87") (name "unconnected-(U4-RS-Pad8)") (class "Default")
      (node (ref "U4") (pin "8") (pinfunction "RS_8") (pintype "passive"))
    )
    (net (code "88") (name "unconnected-(USB1-ID-Pad4)") (class "Default")
      (node (ref "USB1") (pin "4") (pinfunction "ID_4") (pintype "passive"))
    )
  )
)
